# Grove_-_Relay_v1_2.net
KiCad netlist of a schematic drawn in EAGLE
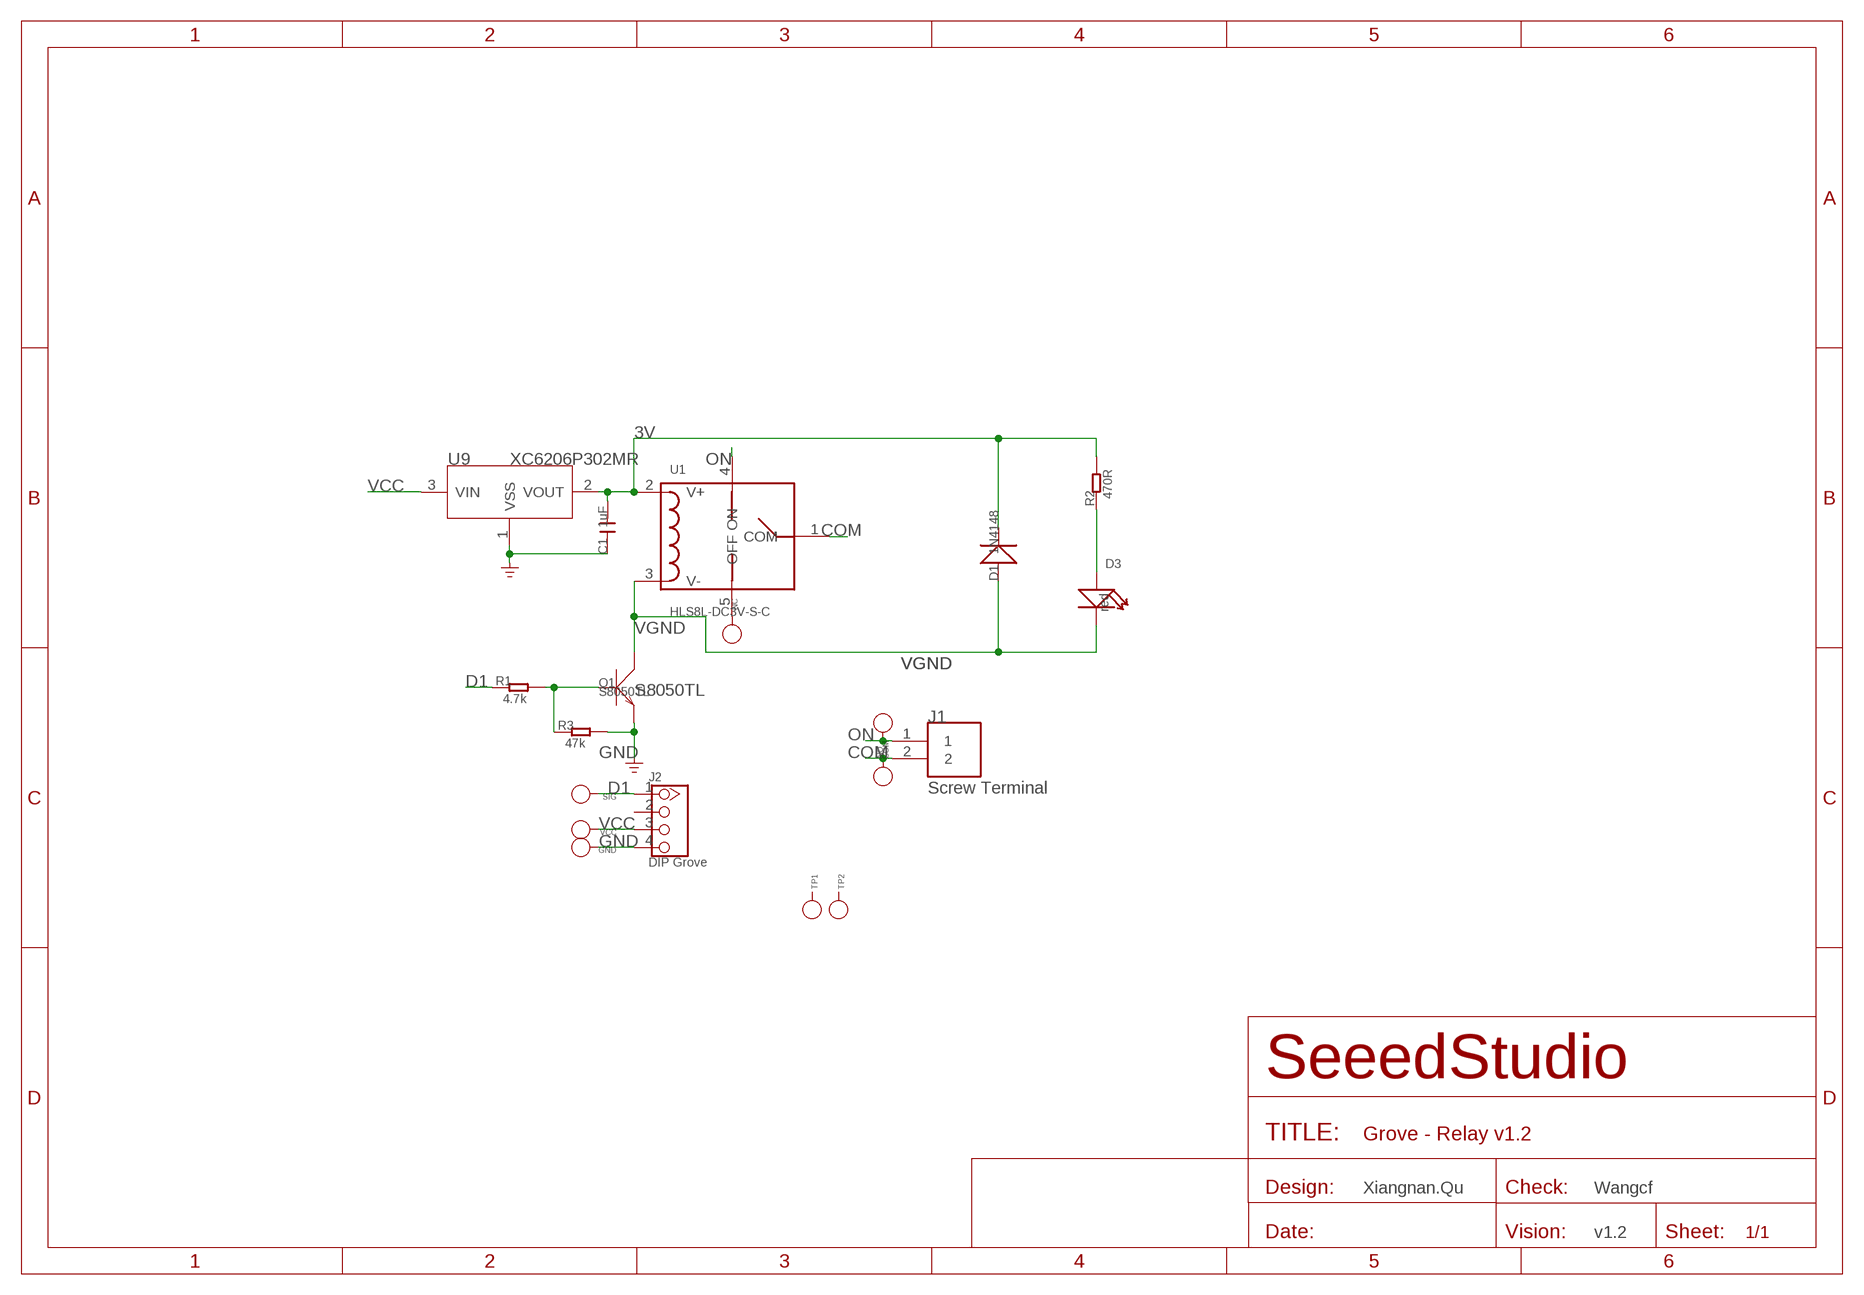
[diagram p0: schematic, sheet 1]

(export (version "E")
  (design (tool "Eeschema 10.0.6"))
  (components
    (comp (ref "C1")
      (value "1uF")
      (footprint "eagle-import:C0603")
      (libsource (lib "eagle-import") (part "C-0603"))
    )
    (comp (ref "COM")
      (value "PAD-TEST-POINT'4545'")
      (footprint "eagle-import:TP_4545")
      (fields (field (name "PARTNO") "DNP"))
      (libsource (lib "eagle-import") (part "PAD-TEST-POINT'4545'"))
    )
    (comp (ref "D1")
      (value "1N4148")
      (footprint "eagle-import:LL-34")
      (libsource (lib "eagle-import") (part "D'1N4148-SMD'"))
    )
    (comp (ref "D3")
      (value "red")
      (footprint "eagle-import:LED-0603")
      (libsource (lib "eagle-import") (part "LED'0603'"))
    )
    (comp (ref "GND")
      (value "PAD-TEST-POINT'4545'")
      (footprint "eagle-import:TP_4545")
      (fields (field (name "PARTNO") "DNP"))
      (libsource (lib "eagle-import") (part "PAD-TEST-POINT'4545'"))
    )
    (comp (ref "J1")
      (value "Screw Terminal")
      (footprint "eagle-import:CON2")
      (libsource (lib "eagle-import") (part "CON2"))
    )
    (comp (ref "J2")
      (value "DIP Grove")
      (footprint "eagle-import:2.0_1X4")
      (libsource (lib "eagle-import") (part "TWIG_2.0"))
    )
    (comp (ref "NC")
      (value "PAD-TEST-POINT'4545'")
      (footprint "eagle-import:TP_4545")
      (fields (field (name "PARTNO") "DNP"))
      (libsource (lib "eagle-import") (part "PAD-TEST-POINT'4545'"))
    )
    (comp (ref "NO")
      (value "PAD-TEST-POINT'4545'")
      (footprint "eagle-import:TP_4545")
      (fields (field (name "PARTNO") "DNP"))
      (libsource (lib "eagle-import") (part "PAD-TEST-POINT'4545'"))
    )
    (comp (ref "Q1")
      (value "S8050TL")
      (footprint "eagle-import:SOT23")
      (libsource (lib "eagle-import") (part "TRANSISTOR-NPN-SOT23"))
    )
    (comp (ref "R1")
      (value "4.7k")
      (footprint "eagle-import:R0603")
      (libsource (lib "eagle-import") (part "R-0603"))
    )
    (comp (ref "R2")
      (value "470R")
      (footprint "eagle-import:R0603")
      (libsource (lib "eagle-import") (part "R-0603"))
    )
    (comp (ref "R3")
      (value "47k")
      (footprint "eagle-import:R0603")
      (libsource (lib "eagle-import") (part "R-0603"))
    )
    (comp (ref "SIG")
      (value "PAD-TEST-POINT'4545'")
      (footprint "eagle-import:TP_4545")
      (fields (field (name "PARTNO") "DNP"))
      (libsource (lib "eagle-import") (part "PAD-TEST-POINT'4545'"))
    )
    (comp (ref "TP1")
      (value "PAD-TEST-POINT'4545'")
      (footprint "eagle-import:TP_4545")
      (fields (field (name "PARTNO") "DNP"))
      (libsource (lib "eagle-import") (part "PAD-TEST-POINT'4545'"))
    )
    (comp (ref "TP2")
      (value "PAD-TEST-POINT'4545'")
      (footprint "eagle-import:TP_4545")
      (fields (field (name "PARTNO") "DNP"))
      (libsource (lib "eagle-import") (part "PAD-TEST-POINT'4545'"))
    )
    (comp (ref "U1")
      (value "HLS8L-DC3V-S-C")
      (footprint "eagle-import:RELAY")
      (libsource (lib "eagle-import") (part "RELAY"))
    )
    (comp (ref "U9")
      (value "XC6206P302MR")
      (footprint "eagle-import:SOT23")
      (libsource (lib "eagle-import") (part "XC6206MR"))
    )
    (comp (ref "VCC")
      (value "PAD-TEST-POINT'4545'")
      (footprint "eagle-import:TP_4545")
      (fields (field (name "PARTNO") "DNP"))
      (libsource (lib "eagle-import") (part "PAD-TEST-POINT'4545'"))
    )
  )
  (nets
    (net (code "1") (name "/3V") (class "Default")
      (node (ref "C1") (pin "2") (pinfunction "2_2") (pintype "passive"))
      (node (ref "D1") (pin "C") (pinfunction "-_C") (pintype "passive"))
      (node (ref "R2") (pin "2") (pinfunction "2_2") (pintype "passive"))
      (node (ref "U1") (pin "2") (pinfunction "V+_2") (pintype "bidirectional"))
      (node (ref "U9") (pin "2") (pinfunction "VOUT_2") (pintype "output"))
    )
    (net (code "2") (name "/COM") (class "Default")
      (node (ref "COM") (pin "T") (pinfunction "T_T") (pintype "bidirectional"))
      (node (ref "J1") (pin "2") (pinfunction "2_2") (pintype "bidirectional"))
      (node (ref "U1") (pin "1") (pinfunction "COM_1") (pintype "bidirectional"))
    )
    (net (code "3") (name "/D1") (class "Default")
      (node (ref "J2") (pin "1") (pinfunction "1_1") (pintype "bidirectional"))
      (node (ref "R1") (pin "1") (pinfunction "1_1") (pintype "passive"))
      (node (ref "SIG") (pin "T") (pinfunction "T_T") (pintype "bidirectional"))
    )
    (net (code "4") (name "/ON") (class "Default")
      (node (ref "J1") (pin "1") (pinfunction "1_1") (pintype "bidirectional"))
      (node (ref "NO") (pin "T") (pinfunction "T_T") (pintype "bidirectional"))
      (node (ref "U1") (pin "4") (pinfunction "ON_4") (pintype "bidirectional"))
    )
    (net (code "5") (name "/VCC") (class "Default")
      (node (ref "J2") (pin "3") (pinfunction "3_3") (pintype "bidirectional"))
      (node (ref "U9") (pin "3") (pinfunction "VIN_3") (pintype "input"))
      (node (ref "VCC") (pin "T") (pinfunction "T_T") (pintype "bidirectional"))
    )
    (net (code "6") (name "/VGND") (class "Default")
      (node (ref "D1") (pin "A") (pinfunction "+_A") (pintype "passive"))
      (node (ref "D3") (pin "-") (pinfunction "-_-") (pintype "passive"))
      (node (ref "Q1") (pin "3") (pinfunction "C_3") (pintype "passive"))
      (node (ref "U1") (pin "3") (pinfunction "V-_3") (pintype "bidirectional"))
    )
    (net (code "7") (name "GND_POWER") (class "Default")
      (node (ref "C1") (pin "1") (pinfunction "1_1") (pintype "passive"))
      (node (ref "GND") (pin "T") (pinfunction "T_T") (pintype "bidirectional"))
      (node (ref "J2") (pin "4") (pinfunction "4_4") (pintype "bidirectional"))
      (node (ref "Q1") (pin "2") (pinfunction "E_2") (pintype "passive"))
      (node (ref "R3") (pin "2") (pinfunction "2_2") (pintype "passive"))
      (node (ref "U9") (pin "1") (pinfunction "VSS_1") (pintype "power_in"))
    )
    (net (code "8") (name "Net-(D3-Pad+)") (class "Default")
      (node (ref "D3") (pin "+") (pinfunction "+_+") (pintype "passive"))
      (node (ref "R2") (pin "1") (pinfunction "1_1") (pintype "passive"))
    )
    (net (code "9") (name "Net-(Q1-B)") (class "Default")
      (node (ref "Q1") (pin "1") (pinfunction "B_1") (pintype "passive"))
      (node (ref "R1") (pin "2") (pinfunction "2_2") (pintype "passive"))
      (node (ref "R3") (pin "1") (pinfunction "1_1") (pintype "passive"))
    )
    (net (code "10") (name "Net-(U1-OFF)") (class "Default")
      (node (ref "NC") (pin "T") (pinfunction "T_T") (pintype "bidirectional"))
      (node (ref "U1") (pin "5") (pinfunction "OFF_5") (pintype "bidirectional"))
    )
    (net (code "11") (name "unconnected-(J2-Pad2)") (class "Default")
      (node (ref "J2") (pin "2") (pinfunction "2_2") (pintype "bidirectional"))
    )
    (net (code "12") (name "unconnected-(TP1-PadT)") (class "Default")
      (node (ref "TP1") (pin "T") (pinfunction "T_T") (pintype "bidirectional"))
    )
    (net (code "13") (name "unconnected-(TP2-PadT)") (class "Default")
      (node (ref "TP2") (pin "T") (pinfunction "T_T") (pintype "bidirectional"))
    )
  )
)
